# PA-HF_100W.net
KiCad netlist of a schematic drawn in Altium Designer
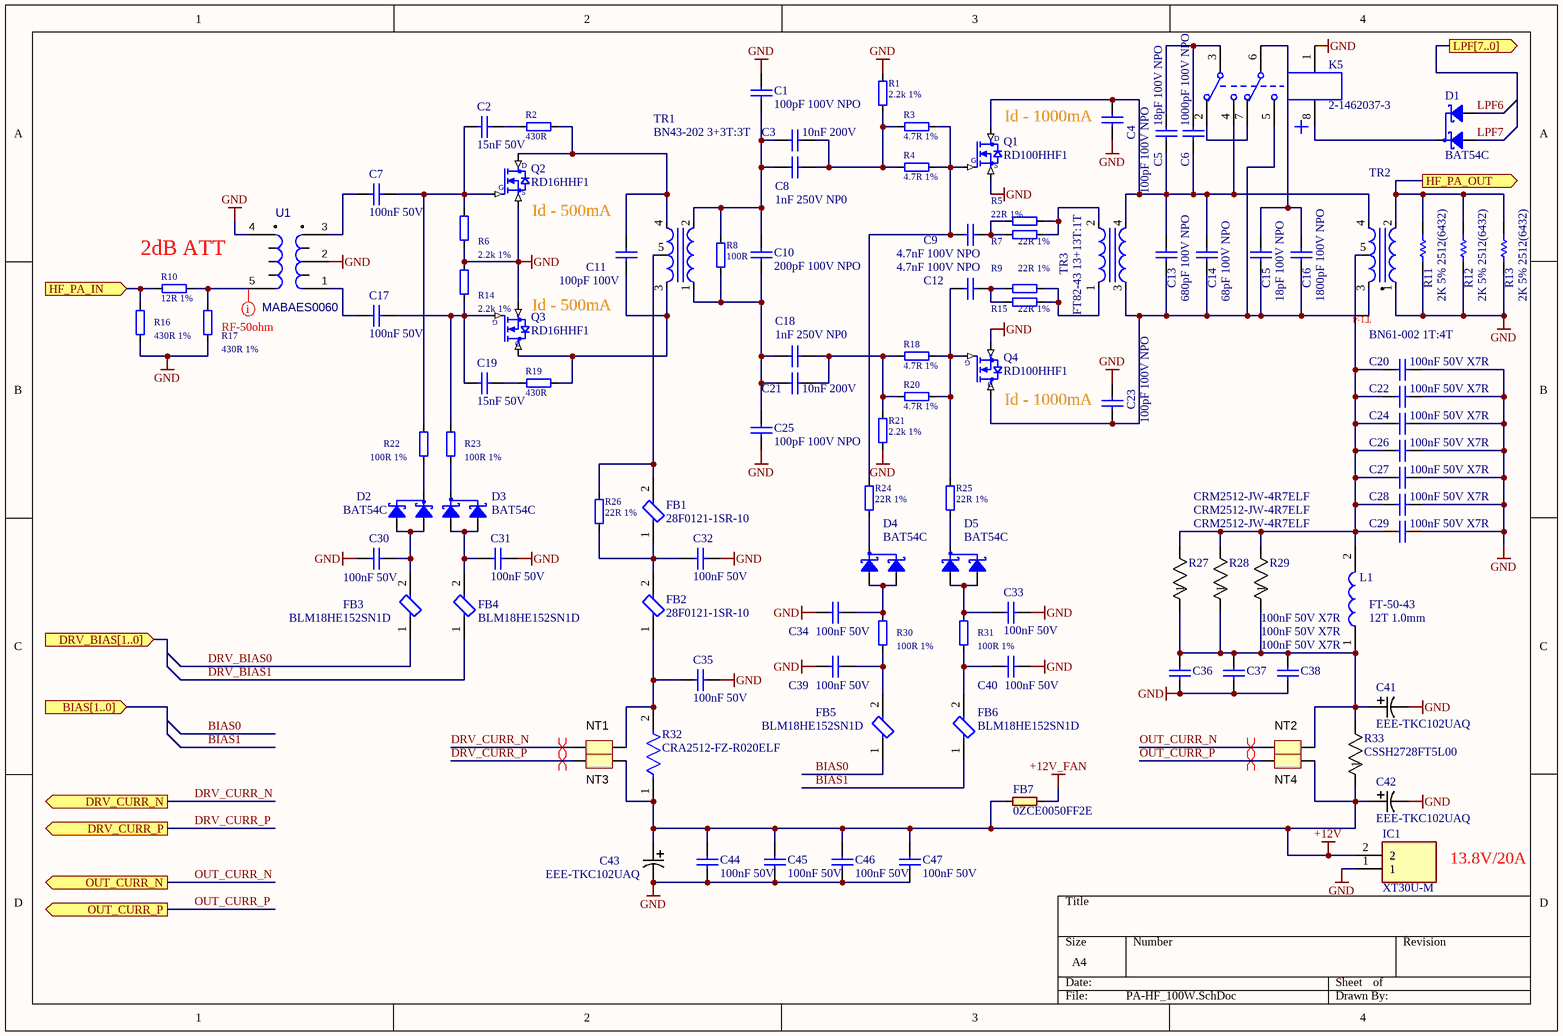
[diagram p0: PA-HF_100W.SchDoc]

(export (version "E")
  (design (tool "Eeschema 10.0.6"))
  (components
    (comp (ref "C1")
      (value "100pF 100V NPO")
      (footprint "C-1206")
      (description "Ceramic Multilayer Capacitor")
      (libsource (lib "Hristo") (part "C semi"))
    )
    (comp (ref "C2")
      (value "15nF 50V")
      (footprint "C-0805")
      (description "Ceramic Multilayer Capacitor")
      (libsource (lib "Hristo") (part "C semi"))
    )
    (comp (ref "C3")
      (value "10nF 200V")
      (footprint "C-1206")
      (description "Ceramic Multilayer Capacitor")
      (libsource (lib "Hristo") (part "C semi"))
    )
    (comp (ref "C4")
      (value "100pF 100V NPO")
      (footprint "C-1206")
      (description "Ceramic Multilayer Capacitor")
      (libsource (lib "Hristo") (part "C semi"))
    )
    (comp (ref "C5")
      (value "18pF 100V NPO")
      (footprint "C-1206")
      (description "Ceramic Multilayer Capacitor")
      (libsource (lib "Hristo") (part "C semi"))
    )
    (comp (ref "C6")
      (value "1000pF 100V NPO")
      (footprint "C-1206")
      (description "Ceramic Multilayer Capacitor")
      (libsource (lib "Hristo") (part "C semi"))
    )
    (comp (ref "C7")
      (value "100nF 50V")
      (footprint "C-0805")
      (description "Ceramic Multilayer Capacitor")
      (libsource (lib "Hristo") (part "C semi"))
    )
    (comp (ref "C8")
      (value "1nF 250V NP0")
      (footprint "C-1206")
      (description "Ceramic Multilayer Capacitor")
      (libsource (lib "Hristo") (part "C semi"))
    )
    (comp (ref "C9")
      (value "4.7nF 100V NPO")
      (footprint "C-1206")
      (description "Ceramic Multilayer Capacitor")
      (libsource (lib "Hristo") (part "C semi"))
    )
    (comp (ref "C10")
      (value "200pF 100V NPO")
      (footprint "C-1206")
      (description "Ceramic Multilayer Capacitor")
      (libsource (lib "Hristo") (part "C semi"))
    )
    (comp (ref "C11")
      (value "100pF 100V")
      (footprint "C-0805")
      (description "Ceramic Multilayer Capacitor")
      (libsource (lib "Hristo") (part "C semi"))
    )
    (comp (ref "C12")
      (value "4.7nF 100V NPO")
      (footprint "C-1206")
      (description "Ceramic Multilayer Capacitor")
      (libsource (lib "Hristo") (part "C semi"))
    )
    (comp (ref "C13")
      (value "680pF 100V NPO")
      (footprint "C-1206")
      (description "Ceramic Multilayer Capacitor")
      (libsource (lib "Hristo") (part "C semi"))
    )
    (comp (ref "C14")
      (value "68pF 100V NPO")
      (footprint "C-1206")
      (description "Ceramic Multilayer Capacitor")
      (libsource (lib "Hristo") (part "C semi"))
    )
    (comp (ref "C15")
      (value "18pF 100V NPO")
      (footprint "C-1206")
      (description "Ceramic Multilayer Capacitor")
      (libsource (lib "Hristo") (part "C semi"))
    )
    (comp (ref "C16")
      (value "1800pF 100V NPO")
      (footprint "C-1206")
      (description "Ceramic Multilayer Capacitor")
      (libsource (lib "Hristo") (part "C semi"))
    )
    (comp (ref "C17")
      (value "100nF 50V")
      (footprint "C-0805")
      (description "Ceramic Multilayer Capacitor")
      (libsource (lib "Hristo") (part "C semi"))
    )
    (comp (ref "C18")
      (value "1nF 250V NP0")
      (footprint "C-1206")
      (description "Ceramic Multilayer Capacitor")
      (libsource (lib "Hristo") (part "C semi"))
    )
    (comp (ref "C19")
      (value "15nF 50V")
      (footprint "C-0805")
      (description "Ceramic Multilayer Capacitor")
      (libsource (lib "Hristo") (part "C semi"))
    )
    (comp (ref "C20")
      (value "100nF 50V X7R")
      (footprint "C-1206")
      (description "Ceramic Multilayer Capacitor")
      (libsource (lib "Hristo") (part "C semi"))
    )
    (comp (ref "C21")
      (value "10nF 200V")
      (footprint "C-1206")
      (description "Ceramic Multilayer Capacitor")
      (libsource (lib "Hristo") (part "C semi"))
    )
    (comp (ref "C22")
      (value "100nF 50V X7R")
      (footprint "C-1206")
      (description "Ceramic Multilayer Capacitor")
      (libsource (lib "Hristo") (part "C semi"))
    )
    (comp (ref "C23")
      (value "100pF 100V NPO")
      (footprint "C-1206")
      (description "Ceramic Multilayer Capacitor")
      (libsource (lib "Hristo") (part "C semi"))
    )
    (comp (ref "C24")
      (value "100nF 50V X7R")
      (footprint "C-1206")
      (description "Ceramic Multilayer Capacitor")
      (libsource (lib "Hristo") (part "C semi"))
    )
    (comp (ref "C25")
      (value "100pF 100V NPO")
      (footprint "C-1206")
      (description "Ceramic Multilayer Capacitor")
      (libsource (lib "Hristo") (part "C semi"))
    )
    (comp (ref "C26")
      (value "100nF 50V X7R")
      (footprint "C-1206")
      (description "Ceramic Multilayer Capacitor")
      (libsource (lib "Hristo") (part "C semi"))
    )
    (comp (ref "C27")
      (value "100nF 50V X7R")
      (footprint "C-1206")
      (description "Ceramic Multilayer Capacitor")
      (libsource (lib "Hristo") (part "C semi"))
    )
    (comp (ref "C28")
      (value "100nF 50V X7R")
      (footprint "C-1206")
      (description "Ceramic Multilayer Capacitor")
      (libsource (lib "Hristo") (part "C semi"))
    )
    (comp (ref "C29")
      (value "100nF 50V X7R")
      (footprint "C-1206")
      (description "Ceramic Multilayer Capacitor")
      (libsource (lib "Hristo") (part "C semi"))
    )
    (comp (ref "C30")
      (value "100nF 50V")
      (footprint "C-0805")
      (description "Ceramic Multilayer Capacitor")
      (libsource (lib "Hristo") (part "C semi"))
    )
    (comp (ref "C31")
      (value "100nF 50V")
      (footprint "C-0805")
      (description "Ceramic Multilayer Capacitor")
      (libsource (lib "Hristo") (part "C semi"))
    )
    (comp (ref "C32")
      (value "100nF 50V")
      (footprint "C-0805")
      (description "Ceramic Multilayer Capacitor")
      (libsource (lib "Hristo") (part "C semi"))
    )
    (comp (ref "C33")
      (value "100nF 50V")
      (footprint "C-0805")
      (description "Ceramic Multilayer Capacitor")
      (libsource (lib "Hristo") (part "C semi"))
    )
    (comp (ref "C34")
      (value "100nF 50V")
      (footprint "C-0805")
      (description "Ceramic Multilayer Capacitor")
      (libsource (lib "Hristo") (part "C semi"))
    )
    (comp (ref "C35")
      (value "100nF 50V")
      (footprint "C-0805")
      (description "Ceramic Multilayer Capacitor")
      (libsource (lib "Hristo") (part "C semi"))
    )
    (comp (ref "C36")
      (value "100nF 50V X7R")
      (footprint "C-1206")
      (description "Ceramic Multilayer Capacitor")
      (libsource (lib "Hristo") (part "C semi"))
    )
    (comp (ref "C37")
      (value "100nF 50V X7R")
      (footprint "C-1206")
      (description "Ceramic Multilayer Capacitor")
      (libsource (lib "Hristo") (part "C semi"))
    )
    (comp (ref "C38")
      (value "100nF 50V X7R")
      (footprint "C-1206")
      (description "Ceramic Multilayer Capacitor")
      (libsource (lib "Hristo") (part "C semi"))
    )
    (comp (ref "C39")
      (value "100nF 50V")
      (footprint "C-0805")
      (description "Ceramic Multilayer Capacitor")
      (libsource (lib "Hristo") (part "C semi"))
    )
    (comp (ref "C40")
      (value "100nF 50V")
      (footprint "C-0805")
      (description "Ceramic Multilayer Capacitor")
      (libsource (lib "Hristo") (part "C semi"))
    )
    (comp (ref "C41")
      (value "EEE-TKC102UAQ")
      (footprint "CAP_PAN_EEE_H13_PAN")
      (description "No Description Available")
      (fields (field (name "COPYRIGHT") "Copyright (C) 2022 Ultra Librarian. All rights reserved."))
      (libsource (lib "Hristo") (part "EEE-TKC102UAQ"))
    )
    (comp (ref "C42")
      (value "EEE-TKC102UAQ")
      (footprint "CAP_PAN_EEE_H13_PAN")
      (description "No Description Available")
      (fields (field (name "COPYRIGHT") "Copyright (C) 2022 Ultra Librarian. All rights reserved."))
      (libsource (lib "Hristo") (part "EEE-TKC102UAQ"))
    )
    (comp (ref "C43")
      (value "EEE-TKC102UAQ")
      (footprint "CAP_PAN_EEE_H13_PAN")
      (description "No Description Available")
      (fields (field (name "COPYRIGHT") "Copyright (C) 2022 Ultra Librarian. All rights reserved."))
      (libsource (lib "Hristo") (part "EEE-TKC102UAQ"))
    )
    (comp (ref "C44")
      (value "100nF 50V")
      (footprint "C-0805")
      (description "Ceramic Multilayer Capacitor")
      (libsource (lib "Hristo") (part "C semi"))
    )
    (comp (ref "C45")
      (value "100nF 50V")
      (footprint "C-0805")
      (description "Ceramic Multilayer Capacitor")
      (libsource (lib "Hristo") (part "C semi"))
    )
    (comp (ref "C46")
      (value "100nF 50V")
      (footprint "C-0805")
      (description "Ceramic Multilayer Capacitor")
      (libsource (lib "Hristo") (part "C semi"))
    )
    (comp (ref "C47")
      (value "100nF 50V")
      (footprint "C-0805")
      (description "Ceramic Multilayer Capacitor")
      (libsource (lib "Hristo") (part "C semi"))
    )
    (comp (ref "D1")
      (value "BAT54C")
      (footprint "SOT-23")
      (description "Schottky barrier diodes")
      (fields (field (name "MANUFACTURER") "NXP"))
      (libsource (lib "EXP-SX Power R2.4") (part "D SH SOT23C"))
    )
    (comp (ref "D2")
      (value "BAT54C")
      (footprint "SOT-23")
      (description "Schottky barrier diodes")
      (fields (field (name "MANUFACTURER") "NXP"))
      (libsource (lib "EXP-SX Power R2.4") (part "D SH SOT23C"))
    )
    (comp (ref "D3")
      (value "BAT54C")
      (footprint "SOT-23")
      (description "Schottky barrier diodes")
      (fields (field (name "MANUFACTURER") "NXP"))
      (libsource (lib "EXP-SX Power R2.4") (part "D SH SOT23C"))
    )
    (comp (ref "D4")
      (value "BAT54C")
      (footprint "SOT-23")
      (description "Schottky barrier diodes")
      (fields (field (name "MANUFACTURER") "NXP"))
      (libsource (lib "EXP-SX Power R2.4") (part "D SH SOT23C"))
    )
    (comp (ref "D5")
      (value "BAT54C")
      (footprint "SOT-23")
      (description "Schottky barrier diodes")
      (fields (field (name "MANUFACTURER") "NXP"))
      (libsource (lib "EXP-SX Power R2.4") (part "D SH SOT23C"))
    )
    (comp (ref "FB1")
      (value "28F0121-1SR-10")
      (footprint "FP-28F0121-1SR-10-MFG")
      (description "FERRITE BEAD 96 OHM 2SMD 1LN")
      (libsource (lib "Altium Content Vault") (part "5f30dd21d616792df468990f7003faa"))
    )
    (comp (ref "FB2")
      (value "28F0121-1SR-10")
      (footprint "FP-28F0121-1SR-10-MFG")
      (description "FERRITE BEAD 96 OHM 2SMD 1LN")
      (libsource (lib "Altium Content Vault") (part "5f30dd21d616792df468990f7003faa"))
    )
    (comp (ref "FB3")
      (value "BLM18HE152SN1D")
      (footprint "FP-BLM18-0_15-t0_8-IPC_C")
      (description "Chip Ferrite Bead, 0603, 1500Ω @ 100MHz, 0.5Ω, 25%, 500mA")
      (fields (field (name "TOLERANCE") "25%"))
      (libsource (lib "Altium Content Vault") (part "5f30dd21d616792df468990f7003faa"))
    )
    (comp (ref "FB4")
      (value "BLM18HE152SN1D")
      (footprint "FP-BLM18-0_15-t0_8-IPC_C")
      (description "Chip Ferrite Bead, 0603, 1500Ω @ 100MHz, 0.5Ω, 25%, 500mA")
      (fields (field (name "TOLERANCE") "25%"))
      (libsource (lib "Altium Content Vault") (part "5f30dd21d616792df468990f7003faa"))
    )
    (comp (ref "FB5")
      (value "BLM18HE152SN1D")
      (footprint "FP-BLM18-0_15-t0_8-IPC_C")
      (description "Chip Ferrite Bead, 0603, 1500Ω @ 100MHz, 0.5Ω, 25%, 500mA")
      (fields (field (name "TOLERANCE") "25%"))
      (libsource (lib "Altium Content Vault") (part "5f30dd21d616792df468990f7003faa"))
    )
    (comp (ref "FB6")
      (value "BLM18HE152SN1D")
      (footprint "FP-BLM18-0_15-t0_8-IPC_C")
      (description "Chip Ferrite Bead, 0603, 1500Ω @ 100MHz, 0.5Ω, 25%, 500mA")
      (fields (field (name "TOLERANCE") "25%"))
      (libsource (lib "Altium Content Vault") (part "5f30dd21d616792df468990f7003faa"))
    )
    (comp (ref "FB7")
      (value "0ZCE0050FF2E")
      (footprint "C-0805")
      (description "Chip Ferrite Bead")
      (fields (field (name "MANUFACTURER") "KING CORE"))
      (libsource (lib "Hristo") (part "L BEAD SMD"))
    )
    (comp (ref "IC1")
      (value "XT30U-M")
      (footprint "SamacSys:XT30UM")
      (description "Integrated Circuit")
      (libsource (lib "*") (part "XT30U-M"))
    )
    (comp (ref "K5")
      (value "2-1462037-3")
      (footprint "TECO-2-1462037-3_V")
      (description "Signal Relay, 2 A, 12 VDC, -40 to 85 degC, 8-Pin SMD, RoHS, Tape and Reel")
      (fields (field (name "MANUFACTURER") "TE Connectivity"))
      (libsource (lib "Altium Content Vault") (part "TECO-2-1462037-3"))
    )
    (comp (ref "L1")
      (value "FT-50-43")
      (footprint "Amidon_FT50_43")
      (fields (field (name "ALTIUM_VALUE") "12T 1.0mm"))
      (libsource (lib "Hristo") (part "Amidon"))
    )
    (comp (ref "NT1")
      (value "Net-Tie")
      (footprint "Net-Tie_10mil")
      (description "Single point connection between nets.")
      (fields (field (name "SYMBOLCREATOR") "codlsc") (field (name "PUBLISHER") "Texas Instruments"))
      (libsource (lib "Hristo") (part "Net-Tie"))
    )
    (comp (ref "NT2")
      (value "Net-Tie")
      (footprint "Net-Tie_10mil")
      (description "Single point connection between nets.")
      (fields (field (name "SYMBOLCREATOR") "codlsc") (field (name "PUBLISHER") "Texas Instruments"))
      (libsource (lib "Hristo") (part "Net-Tie"))
    )
    (comp (ref "NT3")
      (value "Net-Tie")
      (footprint "Net-Tie_10mil")
      (description "Single point connection between nets.")
      (fields (field (name "SYMBOLCREATOR") "codlsc") (field (name "PUBLISHER") "Texas Instruments"))
      (libsource (lib "Hristo") (part "Net-Tie"))
    )
    (comp (ref "NT4")
      (value "Net-Tie")
      (footprint "Net-Tie_10mil")
      (description "Single point connection between nets.")
      (fields (field (name "SYMBOLCREATOR") "codlsc") (field (name "PUBLISHER") "Texas Instruments"))
      (libsource (lib "Hristo") (part "Net-Tie"))
    )
    (comp (ref "Q1")
      (value "RD100HHF1")
      (footprint "RD100HHF1")
      (libsource (lib "Hristo") (part "RD100HHF1"))
    )
    (comp (ref "Q2") (value "RD16HHF1") (footprint "RD16HHF1") (libsource (lib "Hristo") (part "RD16HHF1")))
    (comp (ref "Q3") (value "RD16HHF1") (footprint "RD16HHF1") (libsource (lib "Hristo") (part "RD16HHF1")))
    (comp (ref "Q4")
      (value "RD100HHF1")
      (footprint "RD100HHF1")
      (libsource (lib "Hristo") (part "RD100HHF1"))
    )
    (comp (ref "R1")
      (value "2.2k 1%")
      (footprint "R-1206")
      (description "Chip Resistor")
      (libsource (lib "Hristo") (part "RES semi"))
    )
    (comp (ref "R2")
      (value "430R")
      (footprint "R-1206")
      (description "Chip Resistor")
      (libsource (lib "Hristo") (part "RES semi"))
    )
    (comp (ref "R3")
      (value "4.7R 1%")
      (footprint "R-1206")
      (description "Chip Resistor")
      (libsource (lib "Hristo") (part "RES semi"))
    )
    (comp (ref "R4")
      (value "4.7R 1%")
      (footprint "R-1206")
      (description "Chip Resistor")
      (libsource (lib "Hristo") (part "RES semi"))
    )
    (comp (ref "R5")
      (value "22R 1%")
      (footprint "R-1206")
      (description "Chip Resistor")
      (libsource (lib "Hristo") (part "RES semi"))
    )
    (comp (ref "R6")
      (value "2.2k 1%")
      (footprint "R-0805")
      (description "Chip Resistor")
      (libsource (lib "Hristo") (part "RES semi"))
    )
    (comp (ref "R7")
      (value "22R 1%")
      (footprint "R-1206")
      (description "Chip Resistor")
      (libsource (lib "Hristo") (part "RES semi"))
    )
    (comp (ref "R8")
      (value "100R")
      (footprint "R-1206")
      (description "Chip Resistor")
      (libsource (lib "Hristo") (part "RES semi"))
    )
    (comp (ref "R9")
      (value "22R 1%")
      (footprint "R-1206")
      (description "Chip Resistor")
      (libsource (lib "Hristo") (part "RES semi"))
    )
    (comp (ref "R10")
      (value "12R 1%")
      (footprint "R-0805")
      (description "Chip Resistor")
      (libsource (lib "Hristo") (part "RES semi"))
    )
    (comp (ref "R11")
      (value "2K 5% 2512(6432)")
      (footprint "RESC2512(6432)_N")
      (description "2K 1W 5% 2512 (6432 Metric)  SMD")
      (fields (field (name "POWER") "1 W") (field (name "TOLERANCE") "5 %"))
      (libsource (lib "Altium Content Vault") (part "RES"))
    )
    (comp (ref "R12")
      (value "2K 5% 2512(6432)")
      (footprint "RESC2512(6432)_N")
      (description "2K 1W 5% 2512 (6432 Metric)  SMD")
      (fields (field (name "POWER") "1 W") (field (name "TOLERANCE") "5 %"))
      (libsource (lib "Altium Content Vault") (part "RES"))
    )
    (comp (ref "R13")
      (value "2K 5% 2512(6432)")
      (footprint "RESC2512(6432)_N")
      (description "2K 1W 5% 2512 (6432 Metric)  SMD")
      (fields (field (name "POWER") "1 W") (field (name "TOLERANCE") "5 %"))
      (libsource (lib "Altium Content Vault") (part "RES"))
    )
    (comp (ref "R14")
      (value "2.2k 1%")
      (footprint "R-0805")
      (description "Chip Resistor")
      (libsource (lib "Hristo") (part "RES semi"))
    )
    (comp (ref "R15")
      (value "22R 1%")
      (footprint "R-1206")
      (description "Chip Resistor")
      (libsource (lib "Hristo") (part "RES semi"))
    )
    (comp (ref "R16")
      (value "430R 1%")
      (footprint "R-0805")
      (description "Chip Resistor")
      (libsource (lib "Hristo") (part "RES semi"))
    )
    (comp (ref "R17")
      (value "430R 1%")
      (footprint "R-0805")
      (description "Chip Resistor")
      (libsource (lib "Hristo") (part "RES semi"))
    )
    (comp (ref "R18")
      (value "4.7R 1%")
      (footprint "R-1206")
      (description "Chip Resistor")
      (libsource (lib "Hristo") (part "RES semi"))
    )
    (comp (ref "R19")
      (value "430R")
      (footprint "R-1206")
      (description "Chip Resistor")
      (libsource (lib "Hristo") (part "RES semi"))
    )
    (comp (ref "R20")
      (value "4.7R 1%")
      (footprint "R-1206")
      (description "Chip Resistor")
      (libsource (lib "Hristo") (part "RES semi"))
    )
    (comp (ref "R21")
      (value "2.2k 1%")
      (footprint "R-1206")
      (description "Chip Resistor")
      (libsource (lib "Hristo") (part "RES semi"))
    )
    (comp (ref "R22")
      (value "100R 1%")
      (footprint "R-0805")
      (description "Chip Resistor")
      (libsource (lib "Hristo") (part "RES semi"))
    )
    (comp (ref "R23")
      (value "100R 1%")
      (footprint "R-0805")
      (description "Chip Resistor")
      (libsource (lib "Hristo") (part "RES semi"))
    )
    (comp (ref "R24")
      (value "22R 1%")
      (footprint "R-1206")
      (description "Chip Resistor")
      (libsource (lib "Hristo") (part "RES semi"))
    )
    (comp (ref "R25")
      (value "22R 1%")
      (footprint "R-1206")
      (description "Chip Resistor")
      (libsource (lib "Hristo") (part "RES semi"))
    )
    (comp (ref "R26")
      (value "22R 1%")
      (footprint "R-1206")
      (description "Chip Resistor")
      (libsource (lib "Hristo") (part "RES semi"))
    )
    (comp (ref "R27")
      (value "CRM2512-JW-4R7ELF")
      (footprint "BO_CR2512")
      (description "No Description Available")
      (fields (field (name "COPYRIGHT") "Copyright (C) 2022 Ultra Librarian. All rights reserved."))
      (libsource (lib "Hristo") (part "CRM2512-JW-4R7ELF"))
    )
    (comp (ref "R28")
      (value "CRM2512-JW-4R7ELF")
      (footprint "BO_CR2512")
      (description "No Description Available")
      (fields (field (name "COPYRIGHT") "Copyright (C) 2022 Ultra Librarian. All rights reserved."))
      (libsource (lib "Hristo") (part "CRM2512-JW-4R7ELF"))
    )
    (comp (ref "R29")
      (value "CRM2512-JW-4R7ELF")
      (footprint "BO_CR2512")
      (description "No Description Available")
      (fields (field (name "COPYRIGHT") "Copyright (C) 2022 Ultra Librarian. All rights reserved."))
      (libsource (lib "Hristo") (part "CRM2512-JW-4R7ELF"))
    )
    (comp (ref "R30")
      (value "100R 1%")
      (footprint "R-0805")
      (description "Chip Resistor")
      (libsource (lib "Hristo") (part "RES semi"))
    )
    (comp (ref "R31")
      (value "100R 1%")
      (footprint "R-0805")
      (description "Chip Resistor")
      (libsource (lib "Hristo") (part "RES semi"))
    )
    (comp (ref "R32")
      (value "CRA2512-FZ-R020ELF")
      (footprint "FP-CRA2512-IPC_C")
      (description "RES 0.02 OHM 1% 3W 2512")
      (libsource (lib "Altium Content Vault") (part "1029c3af85768c4190bb7ad29bc67b5"))
    )
    (comp (ref "R33")
      (value "CSSH2728FT5L00")
      (footprint "STA_CSSH2728_STP")
      (description "No Description Available")
      (fields (field (name "COPYRIGHT") "Copyright (C) 2022 Ultra Librarian. All rights reserved."))
      (libsource (lib "Hristo") (part "CSSH2728FT5L00"))
    )
    (comp (ref "TR1")
      (value "BN43-202 3+3T:3T")
      (footprint "BN43-202")
      (description "BN43-202 3+3T:3T 0.5mm")
      (libsource (lib "Sch") (part "BN43-202 3+3T{colon}3T"))
    )
    (comp (ref "TR2")
      (value "BN61-002 1T:4T")
      (footprint "BN61-002")
      (description "BN61-002 1T:4T 25ohms coaxial")
      (libsource (lib "Hristo") (part "BN61-002 1T{colon}4T"))
    )
    (comp (ref "TR3")
      (value "FT82-43 13+13T:1T")
      (footprint "Amidon_FT82-43")
      (description "BN43-202 3+3T:3T 0.5mm")
      (libsource (lib "Hristo") (part "FT82-43 13+13T{colon}1T"))
    )
    (comp (ref "U1")
      (value "MABAES0060")
      (footprint "TRANSF_ACORE2")
      (description "1:1")
      (libsource (lib "Hristo") (part "MABAES0060"))
    )
  )
  (nets
    (net (code "7") (name "+12V") (class "Default")
      (node (ref "C42") (pin "1") (pinfunction "1_1") (pintype "passive"))
      (node (ref "C43") (pin "1") (pinfunction "1_1") (pintype "passive"))
      (node (ref "C44") (pin "2") (pinfunction "2_2") (pintype "passive"))
      (node (ref "C45") (pin "2") (pinfunction "2_2") (pintype "passive"))
      (node (ref "C46") (pin "2") (pinfunction "2_2") (pintype "passive"))
      (node (ref "C47") (pin "2") (pinfunction "2_2") (pintype "passive"))
      (node (ref "FB7") (pin "1") (pinfunction "1_1") (pintype "passive"))
      (node (ref "IC1") (pin "2") (pinfunction "2_2") (pintype "passive"))
      (node (ref "NT3") (pin "2") (pinfunction "2_2") (pintype "passive"))
      (node (ref "NT4") (pin "2") (pinfunction "2_2") (pintype "passive"))
      (node (ref "R32") (pin "1") (pinfunction "1_1") (pintype "passive"))
      (node (ref "R33") (pin "1") (pinfunction "1_1") (pintype "passive"))
    )
    (net (code "8") (name "+12V_FAN") (class "Default")
      (node (ref "FB7") (pin "2") (pinfunction "2_2") (pintype "passive"))
    )
    (net (code "9") (name "/BIAS0") (class "Default")
      (node (ref "FB5") (pin "1") (pinfunction "1_1") (pintype "passive"))
    )
    (net (code "10") (name "/BIAS1") (class "Default")
      (node (ref "FB6") (pin "1") (pinfunction "1_1") (pintype "passive"))
    )
    (net (code "12") (name "/DRV_BIAS0") (class "Default")
      (node (ref "FB3") (pin "1") (pinfunction "1_1") (pintype "passive"))
    )
    (net (code "13") (name "/DRV_BIAS1") (class "Default")
      (node (ref "FB4") (pin "1") (pinfunction "1_1") (pintype "passive"))
    )
    (net (code "15") (name "/DRV_CURR_N") (class "Default")
      (node (ref "NT1") (pin "1") (pinfunction "1_1") (pintype "passive"))
    )
    (net (code "16") (name "/DRV_CURR_P") (class "Default")
      (node (ref "NT3") (pin "1") (pinfunction "1_1") (pintype "passive"))
    )
    (net (code "17") (name "/HF_PA_IN") (class "Default")
      (node (ref "R10") (pin "1") (pinfunction "1_1") (pintype "passive"))
      (node (ref "R16") (pin "2") (pinfunction "2_2") (pintype "passive"))
    )
    (net (code "18") (name "/HF_PA_OUT") (class "Default")
      (node (ref "R11") (pin "2") (pinfunction "2_2") (pintype "passive"))
      (node (ref "R12") (pin "2") (pinfunction "2_2") (pintype "passive"))
      (node (ref "R13") (pin "2") (pinfunction "2_2") (pintype "passive"))
      (node (ref "TR2") (pin "2") (pinfunction "2_2") (pintype "passive"))
    )
    (net (code "19") (name "/LPF6") (class "Default") (node (ref "D1") (pin "2") (pintype "passive")))
    (net (code "20") (name "/LPF7") (class "Default") (node (ref "D1") (pin "1") (pintype "passive")))
    (net (code "22") (name "/OUT_CURR_N") (class "Default")
      (node (ref "NT2") (pin "1") (pinfunction "1_1") (pintype "passive"))
    )
    (net (code "23") (name "/OUT_CURR_P") (class "Default")
      (node (ref "NT4") (pin "1") (pinfunction "1_1") (pintype "passive"))
    )
    (net (code "24") (name "GND") (class "Default")
      (node (ref "C1") (pin "1") (pinfunction "1_1") (pintype "passive"))
      (node (ref "C20") (pin "1") (pinfunction "1_1") (pintype "passive"))
      (node (ref "C22") (pin "1") (pinfunction "1_1") (pintype "passive"))
      (node (ref "C23") (pin "1") (pinfunction "1_1") (pintype "passive"))
      (node (ref "C24") (pin "1") (pinfunction "1_1") (pintype "passive"))
      (node (ref "C25") (pin "2") (pinfunction "2_2") (pintype "passive"))
      (node (ref "C26") (pin "1") (pinfunction "1_1") (pintype "passive"))
      (node (ref "C27") (pin "1") (pinfunction "1_1") (pintype "passive"))
      (node (ref "C28") (pin "1") (pinfunction "1_1") (pintype "passive"))
      (node (ref "C29") (pin "1") (pinfunction "1_1") (pintype "passive"))
      (node (ref "C30") (pin "2") (pinfunction "2_2") (pintype "passive"))
      (node (ref "C31") (pin "1") (pinfunction "1_1") (pintype "passive"))
      (node (ref "C32") (pin "1") (pinfunction "1_1") (pintype "passive"))
      (node (ref "C33") (pin "1") (pinfunction "1_1") (pintype "passive"))
      (node (ref "C34") (pin "1") (pinfunction "1_1") (pintype "passive"))
      (node (ref "C35") (pin "1") (pinfunction "1_1") (pintype "passive"))
      (node (ref "C36") (pin "1") (pinfunction "1_1") (pintype "passive"))
      (node (ref "C37") (pin "1") (pinfunction "1_1") (pintype "passive"))
      (node (ref "C38") (pin "1") (pinfunction "1_1") (pintype "passive"))
      (node (ref "C39") (pin "1") (pinfunction "1_1") (pintype "passive"))
      (node (ref "C4") (pin "2") (pinfunction "2_2") (pintype "passive"))
      (node (ref "C40") (pin "1") (pinfunction "1_1") (pintype "passive"))
      (node (ref "C41") (pin "2") (pinfunction "2_2") (pintype "passive"))
      (node (ref "C42") (pin "2") (pinfunction "2_2") (pintype "passive"))
      (node (ref "C43") (pin "2") (pinfunction "2_2") (pintype "passive"))
      (node (ref "C44") (pin "1") (pinfunction "1_1") (pintype "passive"))
      (node (ref "C45") (pin "1") (pinfunction "1_1") (pintype "passive"))
      (node (ref "C46") (pin "1") (pinfunction "1_1") (pintype "passive"))
      (node (ref "C47") (pin "1") (pinfunction "1_1") (pintype "passive"))
      (node (ref "IC1") (pin "1") (pinfunction "1_1") (pintype "passive"))
      (node (ref "K5") (pin "1") (pinfunction "1_1") (pintype "passive"))
      (node (ref "Q1") (pin "1") (pinfunction "S_1") (pintype "input"))
      (node (ref "Q2") (pin "1") (pinfunction "S_1") (pintype "input"))
      (node (ref "Q3") (pin "1") (pinfunction "S_1") (pintype "input"))
      (node (ref "Q4") (pin "1") (pinfunction "S_1") (pintype "input"))
      (node (ref "R1") (pin "2") (pinfunction "2_2") (pintype "passive"))
      (node (ref "R11") (pin "1") (pinfunction "1_1") (pintype "passive"))
      (node (ref "R12") (pin "1") (pinfunction "1_1") (pintype "passive"))
      (node (ref "R13") (pin "1") (pinfunction "1_1") (pintype "passive"))
      (node (ref "R14") (pin "2") (pinfunction "2_2") (pintype "passive"))
      (node (ref "R16") (pin "1") (pinfunction "1_1") (pintype "passive"))
      (node (ref "R17") (pin "1") (pinfunction "1_1") (pintype "passive"))
      (node (ref "R21") (pin "2") (pinfunction "2_2") (pintype "passive"))
      (node (ref "R6") (pin "1") (pinfunction "1_1") (pintype "passive"))
      (node (ref "TR2") (pin "1") (pinfunction "1_1") (pintype "passive"))
      (node (ref "U1") (pin "2") (pinfunction "S2_2") (pintype "passive"))
      (node (ref "U1") (pin "4") (pinfunction "P1_4") (pintype "passive"))
    )
    (net (code "25") (name "Net-(C1-Pad2)") (class "Default")
      (node (ref "C1") (pin "2") (pinfunction "2_2") (pintype "passive"))
      (node (ref "C10") (pin "1") (pinfunction "1_1") (pintype "passive"))
      (node (ref "C3") (pin "1") (pinfunction "1_1") (pintype "passive"))
      (node (ref "C8") (pin "1") (pinfunction "1_1") (pintype "passive"))
      (node (ref "R8") (pin "2") (pinfunction "2_2") (pintype "passive"))
      (node (ref "TR1") (pin "2") (pinfunction "2_2") (pintype "passive"))
    )
    (net (code "26") (name "Net-(C2-Pad1)") (class "Default")
      (node (ref "C2") (pin "1") (pinfunction "1_1") (pintype "passive"))
      (node (ref "C7") (pin "2") (pinfunction "2_2") (pintype "passive"))
      (node (ref "Q2") (pin "2") (pintype "input"))
      (node (ref "R22") (pin "2") (pinfunction "2_2") (pintype "passive"))
      (node (ref "R6") (pin "2") (pinfunction "2_2") (pintype "passive"))
    )
    (net (code "27") (name "Net-(C2-Pad2)") (class "Default")
      (node (ref "C2") (pin "2") (pinfunction "2_2") (pintype "passive"))
      (node (ref "R2") (pin "1") (pinfunction "1_1") (pintype "passive"))
    )
    (net (code "28") (name "Net-(C3-Pad2)") (class "Default")
      (node (ref "C3") (pin "2") (pinfunction "2_2") (pintype "passive"))
      (node (ref "C8") (pin "2") (pinfunction "2_2") (pintype "passive"))
      (node (ref "R1") (pin "1") (pinfunction "1_1") (pintype "passive"))
      (node (ref "R3") (pin "1") (pinfunction "1_1") (pintype "passive"))
      (node (ref "R4") (pin "1") (pinfunction "1_1") (pintype "passive"))
    )
    (net (code "29") (name "Net-(C5-Pad2)") (class "Default")
      (node (ref "C5") (pin "2") (pinfunction "2_2") (pintype "passive"))
      (node (ref "C6") (pin "2") (pinfunction "2_2") (pintype "passive"))
      (node (ref "K5") (pin "3") (pinfunction "3_3") (pintype "passive"))
    )
    (net (code "30") (name "Net-(C9-Pad1)") (class "Default")
      (node (ref "C9") (pin "1") (pinfunction "1_1") (pintype "passive"))
      (node (ref "Q1") (pin "2") (pintype "input"))
      (node (ref "R24") (pin "2") (pinfunction "2_2") (pintype "passive"))
      (node (ref "R3") (pin "2") (pinfunction "2_2") (pintype "passive"))
      (node (ref "R4") (pin "2") (pinfunction "2_2") (pintype "passive"))
    )
    (net (code "31") (name "Net-(C9-Pad2)") (class "Default")
      (node (ref "C9") (pin "2") (pinfunction "2_2") (pintype "passive"))
      (node (ref "R5") (pin "1") (pinfunction "1_1") (pintype "passive"))
      (node (ref "R7") (pin "1") (pinfunction "1_1") (pintype "passive"))
    )
    (net (code "32") (name "Net-(C10-Pad2)") (class "Default")
      (node (ref "C10") (pin "2") (pinfunction "2_2") (pintype "passive"))
      (node (ref "C18") (pin "1") (pinfunction "1_1") (pintype "passive"))
      (node (ref "C21") (pin "1") (pinfunction "1_1") (pintype "passive"))
      (node (ref "C25") (pin "1") (pinfunction "1_1") (pintype "passive"))
      (node (ref "R8") (pin "1") (pinfunction "1_1") (pintype "passive"))
      (node (ref "TR1") (pin "1") (pinfunction "1_1") (pintype "passive"))
    )
    (net (code "33") (name "Net-(C12-Pad1)") (class "Default")
      (node (ref "C12") (pin "1") (pinfunction "1_1") (pintype "passive"))
      (node (ref "Q4") (pin "2") (pintype "input"))
      (node (ref "R18") (pin "2") (pinfunction "2_2") (pintype "passive"))
      (node (ref "R20") (pin "2") (pinfunction "2_2") (pintype "passive"))
      (node (ref "R25") (pin "2") (pinfunction "2_2") (pintype "passive"))
    )
    (net (code "34") (name "Net-(C12-Pad2)") (class "Default")
      (node (ref "C12") (pin "2") (pinfunction "2_2") (pintype "passive"))
      (node (ref "R15") (pin "1") (pinfunction "1_1") (pintype "passive"))
      (node (ref "R9") (pin "1") (pinfunction "1_1") (pintype "passive"))
    )
    (net (code "35") (name "Net-(C15-Pad2)") (class "Default")
      (node (ref "C15") (pin "2") (pinfunction "2_2") (pintype "passive"))
      (node (ref "C16") (pin "1") (pinfunction "1_1") (pintype "passive"))
      (node (ref "K5") (pin "6") (pinfunction "6_6") (pintype "passive"))
    )
    (net (code "36") (name "Net-(C17-Pad2)") (class "Default")
      (node (ref "C17") (pin "2") (pinfunction "2_2") (pintype "passive"))
      (node (ref "C19") (pin "1") (pinfunction "1_1") (pintype "passive"))
      (node (ref "Q3") (pin "2") (pintype "input"))
      (node (ref "R14") (pin "1") (pinfunction "1_1") (pintype "passive"))
      (node (ref "R23") (pin "2") (pinfunction "2_2") (pintype "passive"))
    )
    (net (code "37") (name "Net-(C18-Pad2)") (class "Default")
      (node (ref "C18") (pin "2") (pinfunction "2_2") (pintype "passive"))
      (node (ref "C21") (pin "2") (pinfunction "2_2") (pintype "passive"))
      (node (ref "R18") (pin "1") (pinfunction "1_1") (pintype "passive"))
      (node (ref "R20") (pin "1") (pinfunction "1_1") (pintype "passive"))
      (node (ref "R21") (pin "1") (pinfunction "1_1") (pintype "passive"))
    )
    (net (code "38") (name "Net-(C19-Pad2)") (class "Default")
      (node (ref "C19") (pin "2") (pinfunction "2_2") (pintype "passive"))
      (node (ref "R19") (pin "1") (pinfunction "1_1") (pintype "passive"))
    )
    (net (code "39") (name "Net-(C20-Pad2)") (class "Default")
      (node (ref "C20") (pin "2") (pinfunction "2_2") (pintype "passive"))
      (node (ref "C22") (pin "2") (pinfunction "2_2") (pintype "passive"))
      (node (ref "C24") (pin "2") (pinfunction "2_2") (pintype "passive"))
      (node (ref "C26") (pin "2") (pinfunction "2_2") (pintype "passive"))
      (node (ref "C27") (pin "2") (pinfunction "2_2") (pintype "passive"))
      (node (ref "C28") (pin "2") (pinfunction "2_2") (pintype "passive"))
      (node (ref "C29") (pin "2") (pinfunction "2_2") (pintype "passive"))
      (node (ref "L1") (pin "2") (pinfunction "2_2") (pintype "passive"))
      (node (ref "R27") (pin "2") (pinfunction "2_2") (pintype "passive"))
      (node (ref "R28") (pin "2") (pinfunction "2_2") (pintype "passive"))
      (node (ref "R29") (pin "2") (pinfunction "2_2") (pintype "passive"))
      (node (ref "TR2") (pin "5") (pinfunction "5_5") (pintype "passive"))
    )
    (net (code "40") (name "Net-(C30-Pad1)") (class "Default")
      (node (ref "C30") (pin "1") (pinfunction "1_1") (pintype "passive"))
      (node (ref "D2") (pin "1") (pintype "passive"))
      (node (ref "D2") (pin "2") (pintype "passive"))
      (node (ref "FB3") (pin "2") (pinfunction "2_2") (pintype "passive"))
    )
    (net (code "41") (name "Net-(C31-Pad2)") (class "Default")
      (node (ref "C31") (pin "2") (pinfunction "2_2") (pintype "passive"))
      (node (ref "D3") (pin "1") (pintype "passive"))
      (node (ref "D3") (pin "2") (pintype "passive"))
      (node (ref "FB4") (pin "2") (pinfunction "2_2") (pintype "passive"))
    )
    (net (code "42") (name "Net-(C32-Pad2)") (class "Default")
      (node (ref "C32") (pin "2") (pinfunction "2_2") (pintype "passive"))
      (node (ref "FB1") (pin "1") (pinfunction "1_1") (pintype "passive"))
      (node (ref "FB2") (pin "2") (pinfunction "2_2") (pintype "passive"))
      (node (ref "R26") (pin "1") (pinfunction "1_1") (pintype "passive"))
    )
    (net (code "43") (name "Net-(C33-Pad2)") (class "Default")
      (node (ref "C33") (pin "2") (pinfunction "2_2") (pintype "passive"))
      (node (ref "D5") (pin "1") (pintype "passive"))
      (node (ref "D5") (pin "2") (pintype "passive"))
      (node (ref "R31") (pin "2") (pinfunction "2_2") (pintype "passive"))
    )
    (net (code "44") (name "Net-(C34-Pad2)") (class "Default")
      (node (ref "C34") (pin "2") (pinfunction "2_2") (pintype "passive"))
      (node (ref "D4") (pin "1") (pintype "passive"))
      (node (ref "D4") (pin "2") (pintype "passive"))
      (node (ref "R30") (pin "2") (pinfunction "2_2") (pintype "passive"))
    )
    (net (code "45") (name "Net-(C35-Pad2)") (class "Default")
      (node (ref "C35") (pin "2") (pinfunction "2_2") (pintype "passive"))
      (node (ref "FB2") (pin "1") (pinfunction "1_1") (pintype "passive"))
      (node (ref "NT1") (pin "2") (pinfunction "2_2") (pintype "passive"))
      (node (ref "R32") (pin "2") (pinfunction "2_2") (pintype "passive"))
    )
    (net (code "46") (name "Net-(C36-Pad2)") (class "Default")
      (node (ref "C36") (pin "2") (pinfunction "2_2") (pintype "passive"))
      (node (ref "C37") (pin "2") (pinfunction "2_2") (pintype "passive"))
      (node (ref "C38") (pin "2") (pinfunction "2_2") (pintype "passive"))
      (node (ref "C41") (pin "1") (pinfunction "1_1") (pintype "passive"))
      (node (ref "L1") (pin "1") (pinfunction "1_1") (pintype "passive"))
      (node (ref "NT2") (pin "2") (pinfunction "2_2") (pintype "passive"))
      (node (ref "R27") (pin "1") (pinfunction "1_1") (pintype "passive"))
      (node (ref "R28") (pin "1") (pinfunction "1_1") (pintype "passive"))
      (node (ref "R29") (pin "1") (pinfunction "1_1") (pintype "passive"))
      (node (ref "R33") (pin "2") (pinfunction "2_2") (pintype "passive"))
    )
    (net (code "47") (name "Net-(C39-Pad2)") (class "Default")
      (node (ref "C39") (pin "2") (pinfunction "2_2") (pintype "passive"))
      (node (ref "FB5") (pin "2") (pinfunction "2_2") (pintype "passive"))
      (node (ref "R30") (pin "1") (pinfunction "1_1") (pintype "passive"))
    )
    (net (code "48") (name "Net-(C40-Pad2)") (class "Default")
      (node (ref "C40") (pin "2") (pinfunction "2_2") (pintype "passive"))
      (node (ref "FB6") (pin "2") (pinfunction "2_2") (pintype "passive"))
      (node (ref "R31") (pin "1") (pinfunction "1_1") (pintype "passive"))
    )
    (net (code "49") (name "Net-(D1-Pad3)") (class "Default")
      (node (ref "D1") (pin "3") (pintype "passive"))
      (node (ref "K5") (pin "8") (pinfunction "8_8") (pintype "passive"))
    )
    (net (code "50") (name "Net-(D2-Pad3)") (class "Default")
      (node (ref "D2") (pin "3") (pintype "passive"))
      (node (ref "R22") (pin "1") (pinfunction "1_1") (pintype "passive"))
    )
    (net (code "51") (name "Net-(D3-Pad3)") (class "Default")
      (node (ref "D3") (pin "3") (pintype "passive"))
      (node (ref "R23") (pin "1") (pinfunction "1_1") (pintype "passive"))
    )
    (net (code "52") (name "Net-(D4-Pad3)") (class "Default")
      (node (ref "D4") (pin "3") (pintype "passive"))
      (node (ref "R24") (pin "1") (pinfunction "1_1") (pintype "passive"))
    )
    (net (code "53") (name "Net-(D5-Pad3)") (class "Default")
      (node (ref "D5") (pin "3") (pintype "passive"))
      (node (ref "R25") (pin "1") (pinfunction "1_1") (pintype "passive"))
    )
    (net (code "54") (name "Net-(FB1-Pad2)") (class "Default")
      (node (ref "FB1") (pin "2") (pinfunction "2_2") (pintype "passive"))
      (node (ref "R26") (pin "2") (pinfunction "2_2") (pintype "passive"))
      (node (ref "TR1") (pin "5") (pinfunction "5_5") (pintype "passive"))
    )
    (net (code "55") (name "Net-(K5-Pad2)") (class "Default")
      (node (ref "K5") (pin "2") (pinfunction "2_2") (pintype "passive"))
      (node (ref "K5") (pin "7") (pinfunction "7_7") (pintype "passive"))
    )
    (net (code "56") (name "Net-(Q1-D)") (class "Default")
      (node (ref "C13") (pin "1") (pinfunction "1_1") (pintype "passive"))
      (node (ref "C14") (pin "1") (pinfunction "1_1") (pintype "passive"))
      (node (ref "C4") (pin "1") (pinfunction "1_1") (pintype "passive"))
      (node (ref "C5") (pin "1") (pinfunction "1_1") (pintype "passive"))
      (node (ref "C6") (pin "1") (pinfunction "1_1") (pintype "passive"))
      (node (ref "K5") (pin "4") (pinfunction "4_4") (pintype "passive"))
      (node (ref "Q1") (pin "3") (pinfunction "D_3") (pintype "input"))
      (node (ref "TR2") (pin "4") (pinfunction "4_4") (pintype "passive"))
      (node (ref "TR3") (pin "4") (pinfunction "4_4") (pintype "passive"))
    )
    (net (code "57") (name "Net-(Q2-D)") (class "Default")
      (node (ref "C11") (pin "2") (pinfunction "2_2") (pintype "passive"))
      (node (ref "Q2") (pin "3") (pinfunction "D_3") (pintype "input"))
      (node (ref "R2") (pin "2") (pinfunction "2_2") (pintype "passive"))
      (node (ref "TR1") (pin "4") (pinfunction "4_4") (pintype "passive"))
    )
    (net (code "58") (name "Net-(Q3-D)") (class "Default")
      (node (ref "C11") (pin "1") (pinfunction "1_1") (pintype "passive"))
      (node (ref "Q3") (pin "3") (pinfunction "D_3") (pintype "input"))
      (node (ref "R19") (pin "2") (pinfunction "2_2") (pintype "passive"))
      (node (ref "TR1") (pin "3") (pinfunction "3_3") (pintype "passive"))
    )
    (net (code "59") (name "Net-(Q4-D)") (class "Default")
      (node (ref "C13") (pin "2") (pinfunction "2_2") (pintype "passive"))
      (node (ref "C14") (pin "2") (pinfunction "2_2") (pintype "passive"))
      (node (ref "C15") (pin "1") (pinfunction "1_1") (pintype "passive"))
      (node (ref "C16") (pin "2") (pinfunction "2_2") (pintype "passive"))
      (node (ref "C23") (pin "2") (pinfunction "2_2") (pintype "passive"))
      (node (ref "K5") (pin "5") (pinfunction "5_5") (pintype "passive"))
      (node (ref "Q4") (pin "3") (pinfunction "D_3") (pintype "input"))
      (node (ref "TR2") (pin "3") (pinfunction "3_3") (pintype "passive"))
      (node (ref "TR3") (pin "3") (pinfunction "3_3") (pintype "passive"))
    )
    (net (code "60") (name "Net-(R5-Pad2)") (class "Default")
      (node (ref "R5") (pin "2") (pinfunction "2_2") (pintype "passive"))
      (node (ref "R7") (pin "2") (pinfunction "2_2") (pintype "passive"))
      (node (ref "TR3") (pin "2") (pinfunction "2_2") (pintype "passive"))
    )
    (net (code "61") (name "Net-(R15-Pad2)") (class "Default")
      (node (ref "R15") (pin "2") (pinfunction "2_2") (pintype "passive"))
      (node (ref "R9") (pin "2") (pinfunction "2_2") (pintype "passive"))
      (node (ref "TR3") (pin "1") (pinfunction "1_1") (pintype "passive"))
    )
    (net (code "62") (name "Net-(U1-P2)") (class "Default")
      (node (ref "R10") (pin "2") (pinfunction "2_2") (pintype "passive"))
      (node (ref "R17") (pin "2") (pinfunction "2_2") (pintype "passive"))
      (node (ref "U1") (pin "5") (pinfunction "P2_5") (pintype "passive"))
    )
    (net (code "63") (name "Net-(U1-S1)") (class "Default")
      (node (ref "C7") (pin "1") (pinfunction "1_1") (pintype "passive"))
      (node (ref "U1") (pin "3") (pinfunction "S1_3") (pintype "passive"))
    )
    (net (code "64") (name "Net-(U1-S3)") (class "Default")
      (node (ref "C17") (pin "1") (pinfunction "1_1") (pintype "passive"))
      (node (ref "U1") (pin "1") (pinfunction "S3_1") (pintype "passive"))
    )
  )
)
